# Picobot_14.net
KiCad netlist of a schematic drawn in EAGLE
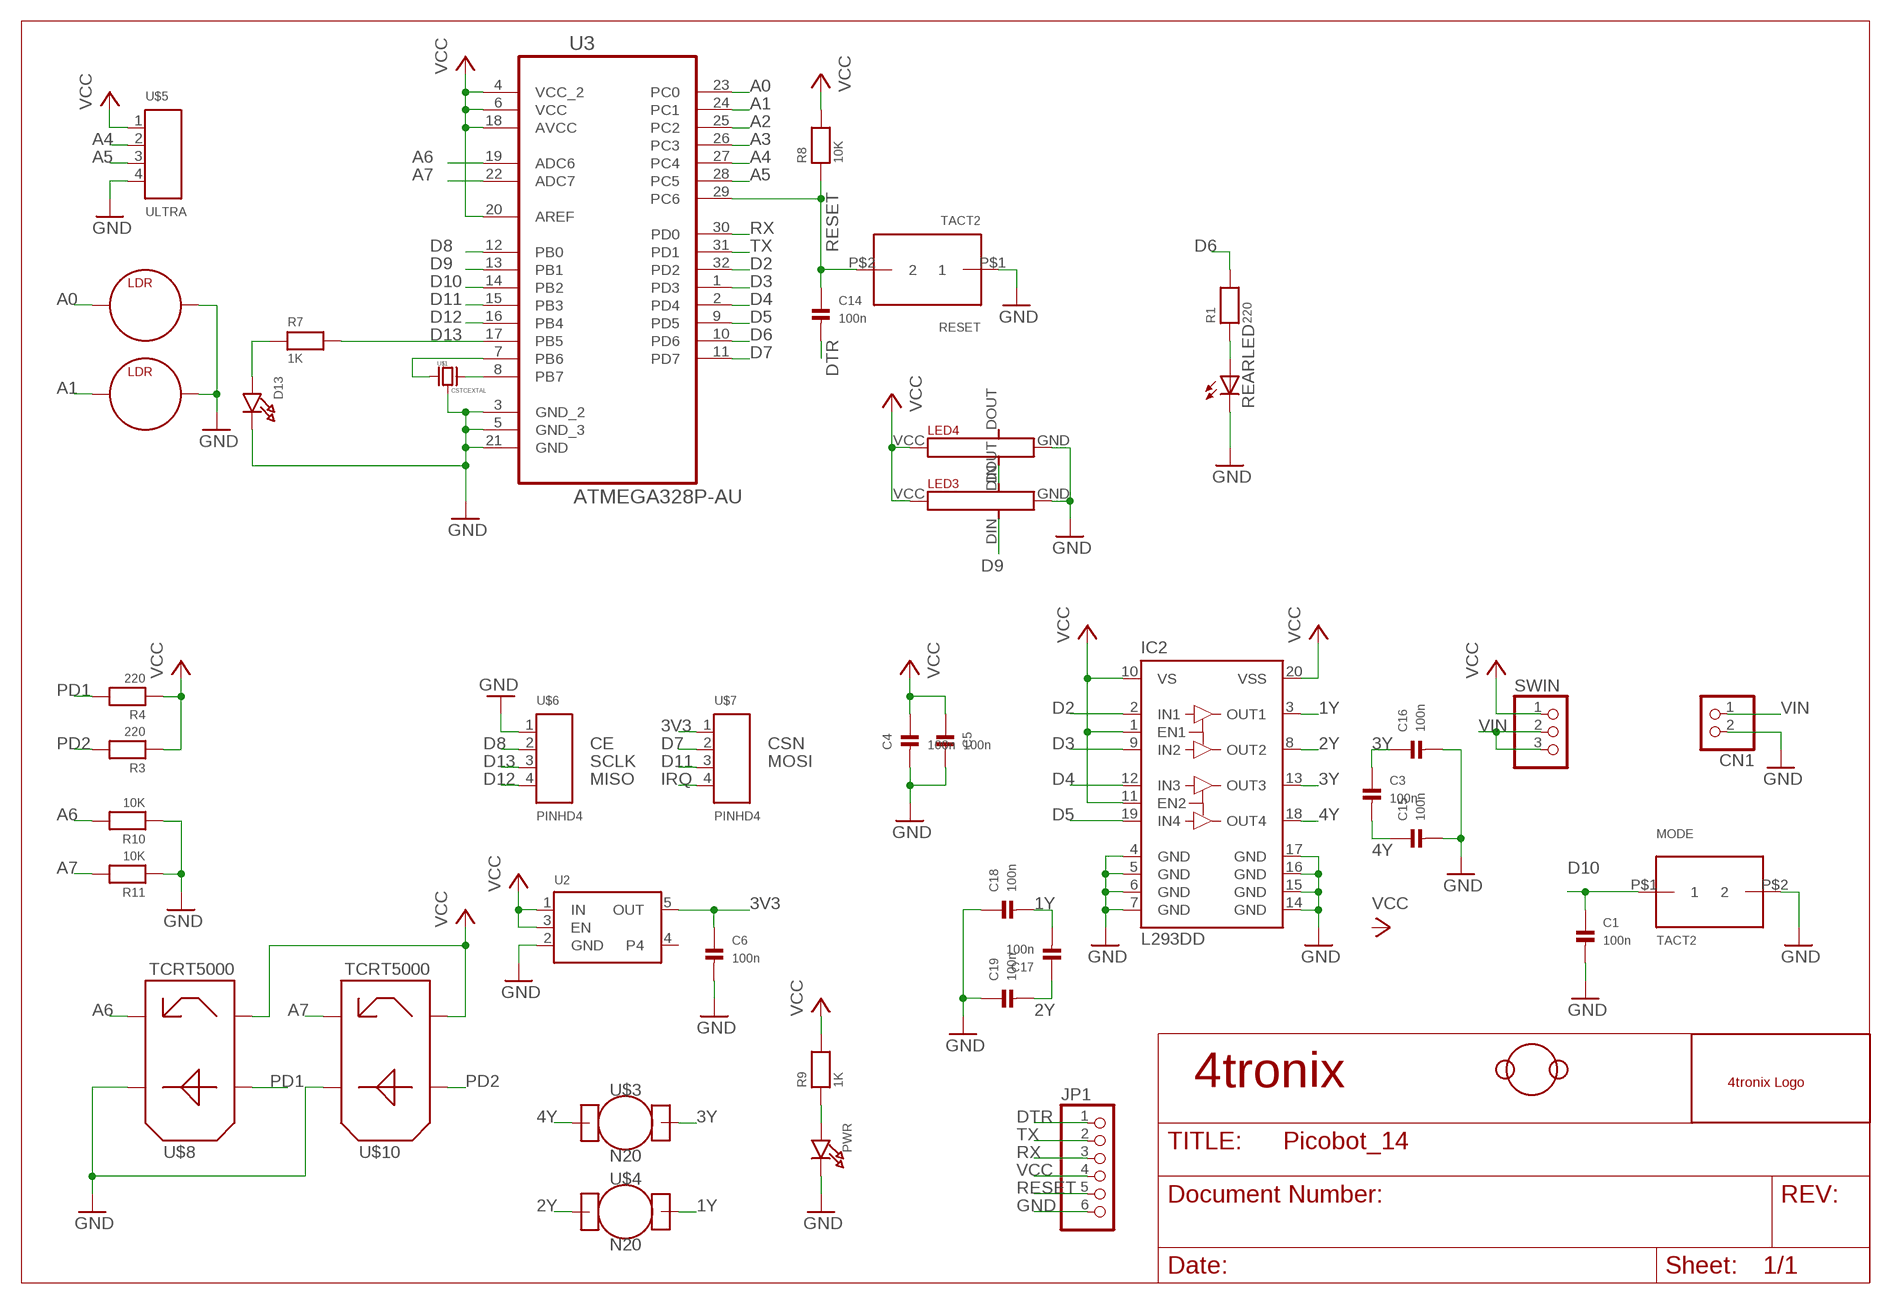
[diagram p0: schematic, sheet 1]

(export (version "E")
  (design (tool "Eeschema 10.0.6"))
  (components
    (comp (ref "C1")
      (value "100n")
      (footprint "eagle-import:_0603MP")
      (libsource (lib "eagle-import") (part "CAP_CERAMIC_0603MP"))
    )
    (comp (ref "C3")
      (value "100n")
      (footprint "eagle-import:_0603MP")
      (libsource (lib "eagle-import") (part "CAP_CERAMIC_0603MP"))
    )
    (comp (ref "C4")
      (value "100n")
      (footprint "eagle-import:_0603MP")
      (libsource (lib "eagle-import") (part "CAP_CERAMIC_0603MP"))
    )
    (comp (ref "C5")
      (value "100n")
      (footprint "eagle-import:_0603MP")
      (libsource (lib "eagle-import") (part "CAP_CERAMIC_0603MP"))
    )
    (comp (ref "C6")
      (value "100n")
      (footprint "eagle-import:_0603MP")
      (libsource (lib "eagle-import") (part "CAP_CERAMIC_0603MP"))
    )
    (comp (ref "C14")
      (value "100n")
      (footprint "eagle-import:_0603MP")
      (libsource (lib "eagle-import") (part "CAP_CERAMIC_0603MP"))
    )
    (comp (ref "C15")
      (value "100n")
      (footprint "eagle-import:_0603MP")
      (libsource (lib "eagle-import") (part "CAP_CERAMIC_0603MP"))
    )
    (comp (ref "C16")
      (value "100n")
      (footprint "eagle-import:_0603MP")
      (libsource (lib "eagle-import") (part "CAP_CERAMIC_0603MP"))
    )
    (comp (ref "C17")
      (value "100n")
      (footprint "eagle-import:_0603MP")
      (libsource (lib "eagle-import") (part "CAP_CERAMIC_0603MP"))
    )
    (comp (ref "C18")
      (value "100n")
      (footprint "eagle-import:_0603MP")
      (libsource (lib "eagle-import") (part "CAP_CERAMIC_0603MP"))
    )
    (comp (ref "C19")
      (value "100n")
      (footprint "eagle-import:_0603MP")
      (libsource (lib "eagle-import") (part "CAP_CERAMIC_0603MP"))
    )
    (comp (ref "CN1")
      (value "JST_2PIN-THM")
      (footprint "eagle-import:JST-PH-2-THM")
      (libsource (lib "eagle-import") (part "JST_2PIN-THM"))
    )
    (comp (ref "D13")
      (value "LED0805_NOOUTLINE")
      (footprint "eagle-import:CHIPLED_0805_NOOUTLINE")
      (libsource (lib "eagle-import") (part "LED0805_NOOUTLINE"))
    )
    (comp (ref "IC2")
      (value "L293DD")
      (footprint "eagle-import:SO20")
      (libsource (lib "eagle-import") (part "L293DD"))
    )
    (comp (ref "JP1")
      (value "PINHD-1X6CB")
      (footprint "eagle-import:1X06-CLEANBIG")
      (libsource (lib "eagle-import") (part "PINHD-1X6CB"))
    )
    (comp (ref "LDR1")
      (value "LDR")
      (footprint "eagle-import:LDR")
      (libsource (lib "eagle-import") (part "LDR"))
    )
    (comp (ref "LDR2")
      (value "LDR")
      (footprint "eagle-import:LDR")
      (libsource (lib "eagle-import") (part "LDR"))
    )
    (comp (ref "LED3")
      (value "WS2812B")
      (footprint "eagle-import:WS2812B")
      (libsource (lib "eagle-import") (part "WS2812B"))
    )
    (comp (ref "LED4")
      (value "WS2812B")
      (footprint "eagle-import:WS2812B")
      (libsource (lib "eagle-import") (part "WS2812B"))
    )
    (comp (ref "MODE")
      (value "TACT2")
      (footprint "eagle-import:TACT2-PIN")
      (libsource (lib "eagle-import") (part "TACT2"))
    )
    (comp (ref "PWR")
      (value "LED0805_NOOUTLINE")
      (footprint "eagle-import:CHIPLED_0805_NOOUTLINE")
      (libsource (lib "eagle-import") (part "LED0805_NOOUTLINE"))
    )
    (comp (ref "R1")
      (value "220")
      (footprint "eagle-import:0603-MINI")
      (libsource (lib "eagle-import") (part "RESISTOR0603MINI"))
    )
    (comp (ref "R3")
      (value "220")
      (footprint "eagle-import:0603-MINI")
      (libsource (lib "eagle-import") (part "RESISTOR0603MINI"))
    )
    (comp (ref "R4")
      (value "220")
      (footprint "eagle-import:0603-MINI")
      (libsource (lib "eagle-import") (part "RESISTOR0603MINI"))
    )
    (comp (ref "R7")
      (value "1K")
      (footprint "eagle-import:0603-MINI")
      (libsource (lib "eagle-import") (part "RESISTOR0603MINI"))
    )
    (comp (ref "R8")
      (value "10K")
      (footprint "eagle-import:0603-MINI")
      (libsource (lib "eagle-import") (part "RESISTOR0603MINI"))
    )
    (comp (ref "R9")
      (value "1K")
      (footprint "eagle-import:0603-MINI")
      (libsource (lib "eagle-import") (part "RESISTOR0603MINI"))
    )
    (comp (ref "R10")
      (value "10K")
      (footprint "eagle-import:0603-MINI")
      (libsource (lib "eagle-import") (part "RESISTOR0603MINI"))
    )
    (comp (ref "R11")
      (value "10K")
      (footprint "eagle-import:0603-MINI")
      (libsource (lib "eagle-import") (part "RESISTOR0603MINI"))
    )
    (comp (ref "REARLED")
      (value "LED3MM")
      (footprint "eagle-import:LED3MM")
      (libsource (lib "eagle-import") (part "LED3MM"))
    )
    (comp (ref "RESET")
      (value "TACT2")
      (footprint "eagle-import:TACT2-PIN")
      (libsource (lib "eagle-import") (part "TACT2"))
    )
    (comp (ref "SWIN")
      (value "PINHD-1X3CB")
      (footprint "eagle-import:1X03-CLEANBIG")
      (libsource (lib "eagle-import") (part "PINHD-1X3CB"))
    )
    (comp (ref "U$1")
      (value "CSTCEXTAL")
      (footprint "eagle-import:CSTCEXTAL")
      (libsource (lib "eagle-import") (part "CSTCEXTAL"))
    )
    (comp (ref "U$2")
      (value "LOGO")
      (footprint "eagle-import:LOGO")
      (libsource (lib "eagle-import") (part "LOGO"))
    )
    (comp (ref "U$3")
      (value "N20")
      (footprint "eagle-import:N20")
      (libsource (lib "eagle-import") (part "N20"))
    )
    (comp (ref "U$4")
      (value "N20")
      (footprint "eagle-import:N20")
      (libsource (lib "eagle-import") (part "N20"))
    )
    (comp (ref "U$5")
      (value "ULTRA")
      (footprint "eagle-import:PINHD4")
      (libsource (lib "eagle-import") (part "PINHD4"))
    )
    (comp (ref "U$6")
      (value "PINHD4")
      (footprint "eagle-import:PINHD4")
      (libsource (lib "eagle-import") (part "PINHD4"))
    )
    (comp (ref "U$7")
      (value "PINHD4")
      (footprint "eagle-import:PINHD4")
      (libsource (lib "eagle-import") (part "PINHD4"))
    )
    (comp (ref "U$8")
      (value "TCRT5000")
      (footprint "eagle-import:TCRT5000")
      (libsource (lib "eagle-import") (part "TCRT5000"))
    )
    (comp (ref "U$9")
      (value "DFRBALL")
      (footprint "eagle-import:DFRBALL")
      (libsource (lib "eagle-import") (part "DFRBALL"))
    )
    (comp (ref "U$10")
      (value "TCRT5000")
      (footprint "eagle-import:TCRT5000")
      (libsource (lib "eagle-import") (part "TCRT5000"))
    )
    (comp (ref "U2")
      (value "VREG_SOT23-5")
      (footprint "eagle-import:SOT23-5")
      (libsource (lib "eagle-import") (part "VREG_SOT23-5"))
    )
    (comp (ref "U3")
      (value "ATMEGA328P-AU")
      (footprint "eagle-import:QFP80P900X900X120-32N")
      (libsource (lib "eagle-import") (part "ATMEGA328P-AU"))
    )
  )
  (nets
    (net (code "1") (name "/1Y") (class "Default")
      (node (ref "C17") (pin "2") (pinfunction "P$2_2") (pintype "passive"))
      (node (ref "C18") (pin "2") (pinfunction "P$2_2") (pintype "passive"))
      (node (ref "IC2") (pin "3") (pinfunction "OUT1_3") (pintype "output"))
      (node (ref "U$4") (pin "MTRA") (pinfunction "MTRB_MTRA") (pintype "bidirectional"))
    )
    (net (code "2") (name "/2Y") (class "Default")
      (node (ref "C17") (pin "1") (pinfunction "P$1_1") (pintype "passive"))
      (node (ref "C19") (pin "2") (pinfunction "P$2_2") (pintype "passive"))
      (node (ref "IC2") (pin "8") (pinfunction "OUT2_8") (pintype "output"))
      (node (ref "U$4") (pin "MTRB") (pinfunction "MTRA_MTRB") (pintype "bidirectional"))
    )
    (net (code "3") (name "/3V3") (class "Default")
      (node (ref "C6") (pin "1") (pinfunction "P$1_1") (pintype "passive"))
      (node (ref "U$7") (pin "1") (pinfunction "1_1") (pintype "bidirectional"))
      (node (ref "U2") (pin "5") (pinfunction "OUT_5") (pintype "bidirectional"))
    )
    (net (code "4") (name "/3Y") (class "Default")
      (node (ref "C16") (pin "1") (pinfunction "P$1_1") (pintype "passive"))
      (node (ref "C3") (pin "1") (pinfunction "P$1_1") (pintype "passive"))
      (node (ref "IC2") (pin "13") (pinfunction "OUT3_13") (pintype "output"))
      (node (ref "U$3") (pin "MTRA") (pinfunction "MTRB_MTRA") (pintype "bidirectional"))
    )
    (net (code "5") (name "/4Y") (class "Default")
      (node (ref "C15") (pin "1") (pinfunction "P$1_1") (pintype "passive"))
      (node (ref "C3") (pin "2") (pinfunction "P$2_2") (pintype "passive"))
      (node (ref "IC2") (pin "18") (pinfunction "OUT4_18") (pintype "output"))
      (node (ref "U$3") (pin "MTRB") (pinfunction "MTRA_MTRB") (pintype "bidirectional"))
    )
    (net (code "6") (name "/A0") (class "Default")
      (node (ref "LDR1") (pin "A") (pinfunction "P$1_A") (pintype "bidirectional"))
      (node (ref "U3") (pin "23") (pinfunction "PC0_23") (pintype "bidirectional"))
    )
    (net (code "7") (name "/A1") (class "Default")
      (node (ref "LDR2") (pin "A") (pinfunction "P$1_A") (pintype "bidirectional"))
      (node (ref "U3") (pin "24") (pinfunction "PC1_24") (pintype "bidirectional"))
    )
    (net (code "8") (name "/A2") (class "Default")
      (node (ref "U3") (pin "25") (pinfunction "PC2_25") (pintype "bidirectional"))
    )
    (net (code "9") (name "/A3") (class "Default")
      (node (ref "U3") (pin "26") (pinfunction "PC3_26") (pintype "bidirectional"))
    )
    (net (code "10") (name "/A4") (class "Default")
      (node (ref "U$5") (pin "2") (pinfunction "2_2") (pintype "bidirectional"))
      (node (ref "U3") (pin "27") (pinfunction "PC4_27") (pintype "bidirectional"))
    )
    (net (code "11") (name "/A5") (class "Default")
      (node (ref "U$5") (pin "3") (pinfunction "3_3") (pintype "bidirectional"))
      (node (ref "U3") (pin "28") (pinfunction "PC5_28") (pintype "bidirectional"))
    )
    (net (code "12") (name "/A6") (class "Default")
      (node (ref "R10") (pin "2") (pinfunction "2_2") (pintype "passive"))
      (node (ref "U$8") (pin "TR2") (pinfunction "TR2_TR2") (pintype "bidirectional"))
      (node (ref "U3") (pin "19") (pinfunction "ADC6_19") (pintype "input"))
    )
    (net (code "13") (name "/A7") (class "Default")
      (node (ref "R11") (pin "2") (pinfunction "2_2") (pintype "passive"))
      (node (ref "U$10") (pin "TR2") (pinfunction "TR2_TR2") (pintype "bidirectional"))
      (node (ref "U3") (pin "22") (pinfunction "ADC7_22") (pintype "input"))
    )
    (net (code "14") (name "/D2") (class "Default")
      (node (ref "IC2") (pin "2") (pinfunction "IN1_2") (pintype "input"))
      (node (ref "U3") (pin "32") (pinfunction "PD2_32") (pintype "bidirectional"))
    )
    (net (code "15") (name "/D3") (class "Default")
      (node (ref "IC2") (pin "9") (pinfunction "IN2_9") (pintype "input"))
      (node (ref "U3") (pin "1") (pinfunction "PD3_1") (pintype "bidirectional"))
    )
    (net (code "16") (name "/D4") (class "Default")
      (node (ref "IC2") (pin "12") (pinfunction "IN3_12") (pintype "input"))
      (node (ref "U3") (pin "2") (pinfunction "PD4_2") (pintype "bidirectional"))
    )
    (net (code "17") (name "/D5") (class "Default")
      (node (ref "IC2") (pin "19") (pinfunction "IN4_19") (pintype "input"))
      (node (ref "U3") (pin "9") (pinfunction "PD5_9") (pintype "bidirectional"))
    )
    (net (code "18") (name "/D6") (class "Default")
      (node (ref "R1") (pin "2") (pinfunction "2_2") (pintype "passive"))
      (node (ref "U3") (pin "10") (pinfunction "PD6_10") (pintype "bidirectional"))
    )
    (net (code "19") (name "/D7") (class "Default")
      (node (ref "U$7") (pin "2") (pinfunction "2_2") (pintype "bidirectional"))
      (node (ref "U3") (pin "11") (pinfunction "PD7_11") (pintype "bidirectional"))
    )
    (net (code "20") (name "/D8") (class "Default")
      (node (ref "U$6") (pin "2") (pinfunction "2_2") (pintype "bidirectional"))
      (node (ref "U3") (pin "12") (pinfunction "PB0_12") (pintype "bidirectional"))
    )
    (net (code "21") (name "/D9") (class "Default")
      (node (ref "LED3") (pin "DIN") (pinfunction "DI_DIN") (pintype "input"))
      (node (ref "U3") (pin "13") (pinfunction "PB1_13") (pintype "bidirectional"))
    )
    (net (code "22") (name "/D10") (class "Default")
      (node (ref "C1") (pin "1") (pinfunction "P$1_1") (pintype "passive"))
      (node (ref "MODE") (pin "P$1") (pinfunction "1_P$1") (pintype "bidirectional"))
      (node (ref "U3") (pin "14") (pinfunction "PB2_14") (pintype "bidirectional"))
    )
    (net (code "23") (name "/D11") (class "Default")
      (node (ref "U$7") (pin "3") (pinfunction "3_3") (pintype "bidirectional"))
      (node (ref "U3") (pin "15") (pinfunction "PB3_15") (pintype "bidirectional"))
    )
    (net (code "24") (name "/D12") (class "Default")
      (node (ref "U$6") (pin "4") (pinfunction "4_4") (pintype "bidirectional"))
      (node (ref "U3") (pin "16") (pinfunction "PB4_16") (pintype "bidirectional"))
    )
    (net (code "25") (name "/D13") (class "Default")
      (node (ref "R7") (pin "2") (pinfunction "2_2") (pintype "passive"))
      (node (ref "U$6") (pin "3") (pinfunction "3_3") (pintype "bidirectional"))
      (node (ref "U3") (pin "17") (pinfunction "PB5_17") (pintype "bidirectional"))
    )
    (net (code "26") (name "/DTR") (class "Default")
      (node (ref "C14") (pin "2") (pinfunction "P$2_2") (pintype "passive"))
      (node (ref "JP1") (pin "1") (pinfunction "1_1") (pintype "passive"))
    )
    (net (code "27") (name "/IRQ") (class "Default")
      (node (ref "U$7") (pin "4") (pinfunction "4_4") (pintype "bidirectional"))
    )
    (net (code "28") (name "/PD1") (class "Default")
      (node (ref "R4") (pin "2") (pinfunction "2_2") (pintype "passive"))
      (node (ref "U$8") (pin "LED1") (pinfunction "LED1_LED1") (pintype "bidirectional"))
    )
    (net (code "29") (name "/PD2") (class "Default")
      (node (ref "R3") (pin "2") (pinfunction "2_2") (pintype "passive"))
      (node (ref "U$10") (pin "LED1") (pinfunction "LED1_LED1") (pintype "bidirectional"))
    )
    (net (code "30") (name "/RESET") (class "Default")
      (node (ref "C14") (pin "1") (pinfunction "P$1_1") (pintype "passive"))
      (node (ref "JP1") (pin "5") (pinfunction "5_5") (pintype "passive"))
      (node (ref "R8") (pin "1") (pinfunction "1_1") (pintype "passive"))
      (node (ref "RESET") (pin "P$2") (pinfunction "2_P$2") (pintype "bidirectional"))
      (node (ref "U3") (pin "29") (pinfunction "PC6_29") (pintype "bidirectional"))
    )
    (net (code "31") (name "/RX") (class "Default")
      (node (ref "JP1") (pin "3") (pinfunction "3_3") (pintype "passive"))
      (node (ref "U3") (pin "30") (pinfunction "PD0_30") (pintype "bidirectional"))
    )
    (net (code "32") (name "/TX") (class "Default")
      (node (ref "JP1") (pin "2") (pinfunction "2_2") (pintype "passive"))
      (node (ref "U3") (pin "31") (pinfunction "PD1_31") (pintype "bidirectional"))
    )
    (net (code "33") (name "/VIN") (class "Default")
      (node (ref "CN1") (pin "1") (pinfunction "2_1") (pintype "passive"))
      (node (ref "SWIN") (pin "2") (pinfunction "2_2") (pintype "passive"))
      (node (ref "SWIN") (pin "3") (pinfunction "3_3") (pintype "passive"))
    )
    (net (code "34") (name "GND") (class "Default")
      (node (ref "C1") (pin "2") (pinfunction "P$2_2") (pintype "passive"))
      (node (ref "C15") (pin "2") (pinfunction "P$2_2") (pintype "passive"))
      (node (ref "C16") (pin "2") (pinfunction "P$2_2") (pintype "passive"))
      (node (ref "C18") (pin "1") (pinfunction "P$1_1") (pintype "passive"))
      (node (ref "C19") (pin "1") (pinfunction "P$1_1") (pintype "passive"))
      (node (ref "C4") (pin "2") (pinfunction "P$2_2") (pintype "passive"))
      (node (ref "C5") (pin "2") (pinfunction "P$2_2") (pintype "passive"))
      (node (ref "C6") (pin "2") (pinfunction "P$2_2") (pintype "passive"))
      (node (ref "CN1") (pin "2") (pinfunction "1_2") (pintype "passive"))
      (node (ref "D13") (pin "C") (pinfunction "C_C") (pintype "passive"))
      (node (ref "IC2") (pin "14") (pinfunction "GND_14") (pintype "power_in"))
      (node (ref "IC2") (pin "15") (pinfunction "GND_15") (pintype "power_in"))
      (node (ref "IC2") (pin "16") (pinfunction "GND_16") (pintype "power_in"))
      (node (ref "IC2") (pin "17") (pinfunction "GND_17") (pintype "power_in"))
      (node (ref "IC2") (pin "4") (pinfunction "GND_4") (pintype "power_in"))
      (node (ref "IC2") (pin "5") (pinfunction "GND_5") (pintype "power_in"))
      (node (ref "IC2") (pin "6") (pinfunction "GND_6") (pintype "power_in"))
      (node (ref "IC2") (pin "7") (pinfunction "GND_7") (pintype "power_in"))
      (node (ref "JP1") (pin "6") (pinfunction "6_6") (pintype "passive"))
      (node (ref "LDR1") (pin "K") (pinfunction "P$2_K") (pintype "bidirectional"))
      (node (ref "LDR2") (pin "K") (pinfunction "P$2_K") (pintype "bidirectional"))
      (node (ref "LED3") (pin "GND") (pinfunction "GND_GND") (pintype "power_in"))
      (node (ref "LED4") (pin "GND") (pinfunction "GND_GND") (pintype "power_in"))
      (node (ref "MODE") (pin "P$2") (pinfunction "2_P$2") (pintype "bidirectional"))
      (node (ref "PWR") (pin "C") (pinfunction "C_C") (pintype "passive"))
      (node (ref "R10") (pin "1") (pinfunction "1_1") (pintype "passive"))
      (node (ref "R11") (pin "1") (pinfunction "1_1") (pintype "passive"))
      (node (ref "REARLED") (pin "K") (pinfunction "C_K") (pintype "passive"))
      (node (ref "RESET") (pin "P$1") (pinfunction "1_P$1") (pintype "bidirectional"))
      (node (ref "U$1") (pin "G") (pinfunction "G_G") (pintype "bidirectional"))
      (node (ref "U$10") (pin "LED2") (pinfunction "LED2_LED2") (pintype "bidirectional"))
      (node (ref "U$5") (pin "4") (pinfunction "4_4") (pintype "bidirectional"))
      (node (ref "U$6") (pin "1") (pinfunction "1_1") (pintype "bidirectional"))
      (node (ref "U$8") (pin "LED2") (pinfunction "LED2_LED2") (pintype "bidirectional"))
      (node (ref "U2") (pin "2") (pinfunction "GND_2") (pintype "bidirectional"))
      (node (ref "U3") (pin "21") (pinfunction "GND_21") (pintype "passive"))
      (node (ref "U3") (pin "3") (pinfunction "GND_2_3") (pintype "passive"))
      (node (ref "U3") (pin "5") (pinfunction "GND_3_5") (pintype "passive"))
    )
    (net (code "35") (name "Net-(D13-PadA)") (class "Default")
      (node (ref "D13") (pin "A") (pinfunction "A_A") (pintype "passive"))
      (node (ref "R7") (pin "1") (pinfunction "1_1") (pintype "passive"))
    )
    (net (code "36") (name "Net-(LED3-DO)") (class "Default")
      (node (ref "LED3") (pin "DOUT") (pinfunction "DO_DOUT") (pintype "output"))
      (node (ref "LED4") (pin "DIN") (pinfunction "DI_DIN") (pintype "input"))
    )
    (net (code "37") (name "Net-(PWR-PadA)") (class "Default")
      (node (ref "PWR") (pin "A") (pinfunction "A_A") (pintype "passive"))
      (node (ref "R9") (pin "1") (pinfunction "1_1") (pintype "passive"))
    )
    (net (code "38") (name "Net-(R1-Pad1)") (class "Default")
      (node (ref "R1") (pin "1") (pinfunction "1_1") (pintype "passive"))
      (node (ref "REARLED") (pin "A") (pinfunction "A_A") (pintype "passive"))
    )
    (net (code "39") (name "Net-(U3-PB6)") (class "Default")
      (node (ref "U$1") (pin "X1") (pinfunction "X1_X1") (pintype "bidirectional"))
      (node (ref "U3") (pin "7") (pinfunction "PB6_7") (pintype "bidirectional"))
    )
    (net (code "40") (name "Net-(U3-PB7)") (class "Default")
      (node (ref "U$1") (pin "X2") (pinfunction "X2_X2") (pintype "bidirectional"))
      (node (ref "U3") (pin "8") (pinfunction "PB7_8") (pintype "bidirectional"))
    )
    (net (code "41") (name "VCC") (class "Default")
      (node (ref "C4") (pin "1") (pinfunction "P$1_1") (pintype "passive"))
      (node (ref "C5") (pin "1") (pinfunction "P$1_1") (pintype "passive"))
      (node (ref "IC2") (pin "1") (pinfunction "EN1_1") (pintype "input"))
      (node (ref "IC2") (pin "10") (pinfunction "VS_10") (pintype "power_in"))
      (node (ref "IC2") (pin "11") (pinfunction "EN2_11") (pintype "input"))
      (node (ref "IC2") (pin "20") (pinfunction "VSS_20") (pintype "power_in"))
      (node (ref "JP1") (pin "4") (pinfunction "4_4") (pintype "passive"))
      (node (ref "LED3") (pin "VCC") (pinfunction "VCC_VCC") (pintype "bidirectional"))
      (node (ref "LED4") (pin "VCC") (pinfunction "VCC_VCC") (pintype "bidirectional"))
      (node (ref "R3") (pin "1") (pinfunction "1_1") (pintype "passive"))
      (node (ref "R4") (pin "1") (pinfunction "1_1") (pintype "passive"))
      (node (ref "R8") (pin "2") (pinfunction "2_2") (pintype "passive"))
      (node (ref "R9") (pin "2") (pinfunction "2_2") (pintype "passive"))
      (node (ref "SWIN") (pin "1") (pinfunction "1_1") (pintype "passive"))
      (node (ref "U$10") (pin "TR1") (pinfunction "TR1_TR1") (pintype "bidirectional"))
      (node (ref "U$5") (pin "1") (pinfunction "1_1") (pintype "bidirectional"))
      (node (ref "U$8") (pin "TR1") (pinfunction "TR1_TR1") (pintype "bidirectional"))
      (node (ref "U2") (pin "1") (pinfunction "IN_1") (pintype "bidirectional"))
      (node (ref "U2") (pin "3") (pinfunction "EN_3") (pintype "bidirectional"))
      (node (ref "U3") (pin "18") (pinfunction "AVCC_18") (pintype "power_in"))
      (node (ref "U3") (pin "20") (pinfunction "AREF_20") (pintype "input"))
      (node (ref "U3") (pin "4") (pinfunction "VCC_2_4") (pintype "power_in"))
      (node (ref "U3") (pin "6") (pinfunction "VCC_6") (pintype "power_in"))
    )
    (net (code "42") (name "unconnected-(LED4-DO-PadDOUT)") (class "Default")
      (node (ref "LED4") (pin "DOUT") (pinfunction "DO_DOUT") (pintype "output"))
    )
    (net (code "43") (name "unconnected-(U2-P4-Pad4)") (class "Default")
      (node (ref "U2") (pin "4") (pinfunction "P4_4") (pintype "bidirectional"))
    )
  )
)
